# ad2addon.net
KiCad netlist of a schematic drawn in Altium Designer
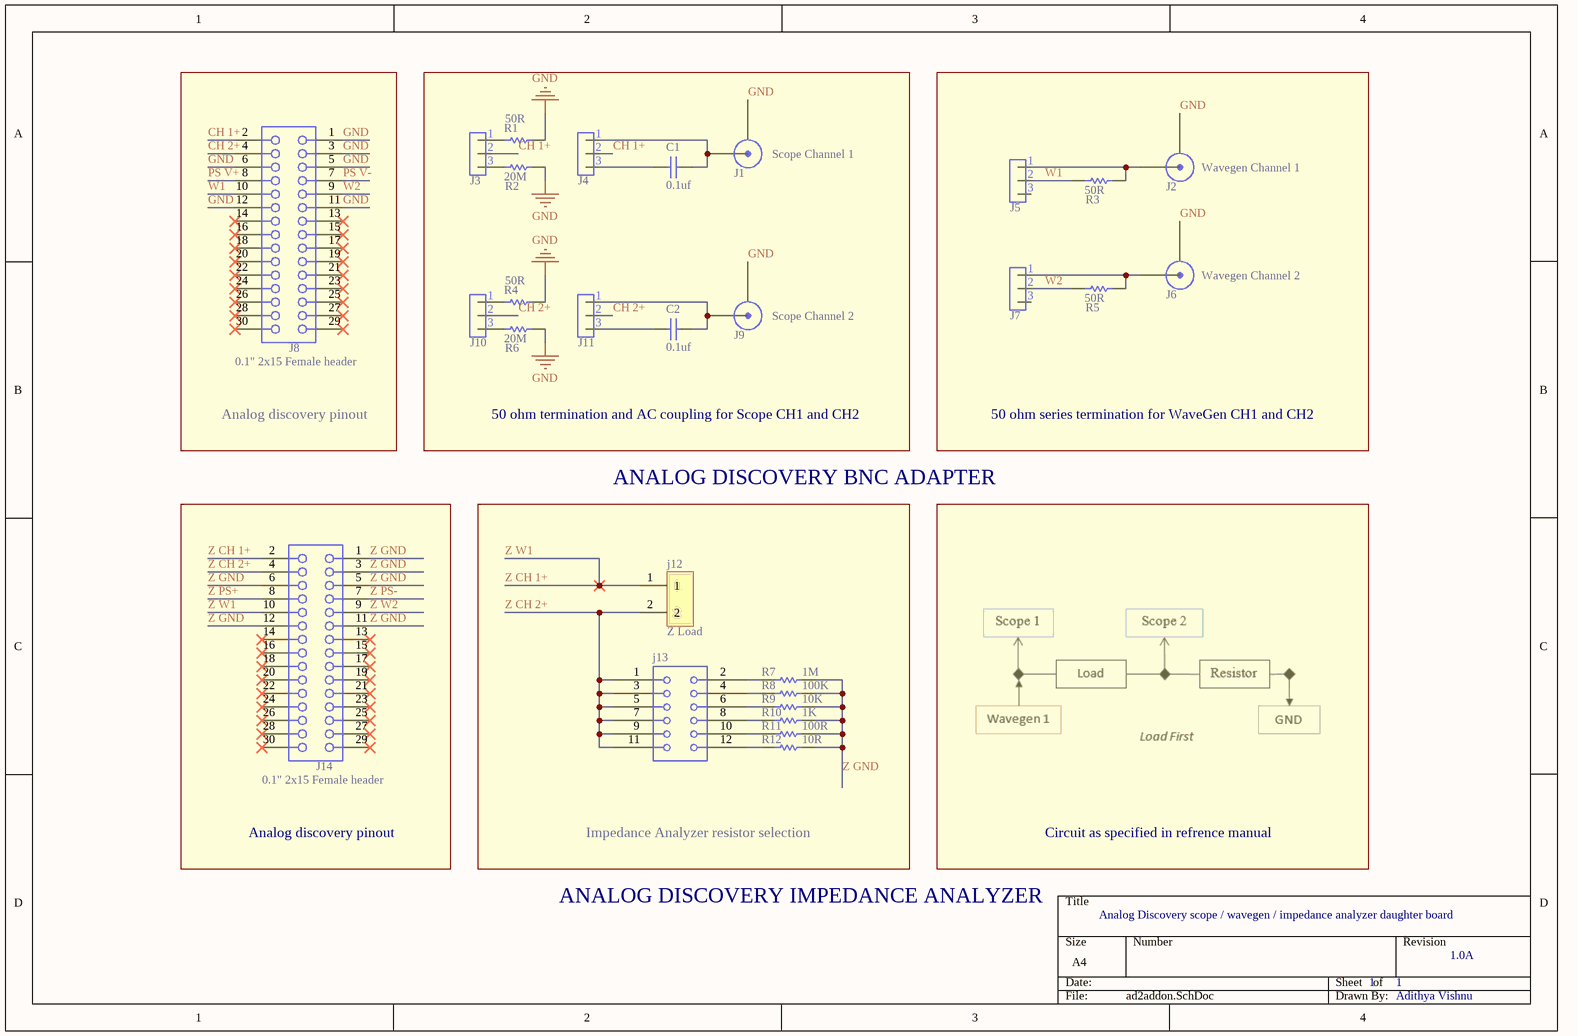
[diagram p0: ad2addon.SchDoc]

(export (version "E")
  (design (tool "Eeschema 10.0.6"))
  (components
    (comp (ref "C1")
      (value "0.1uf")
      (footprint "CAPC2013X94X50NL20T25")
      (description "CAP")
      (libsource (lib "CommunityVault") (part "CMP-126791-4"))
    )
    (comp (ref "C2")
      (value "0.1uf")
      (footprint "CAPC2013X94X50NL20T25")
      (description "CAP")
      (libsource (lib "CommunityVault") (part "CMP-126791-4"))
    )
    (comp (ref "J1")
      (value "Amphenol 031-5431-2010")
      (footprint "PCB-bp7jxlavj6ad2jzc7otg-1")
      (description "Right Angle 50Ohm Thru Hole Bulkhead Fitting BNC Conn, jack, Solder Term Nickel")
      (fields (field (name "PART PLACEMENT") "Scope Channel 1"))
      (libsource (lib "CommunityVault") (part "CMP-8fb544cbd9675072-1"))
    )
    (comp (ref "J2")
      (value "Amphenol 031-5431-2010")
      (footprint "PCB-bp7jxlavj6ad2jzc7otg-1")
      (description "Right Angle 50Ohm Thru Hole Bulkhead Fitting BNC Conn, jack, Solder Term Nickel")
      (fields (field (name "PART PLACEMENT") "Wavegen Channel 1"))
      (libsource (lib "CommunityVault") (part "CMP-8fb544cbd9675072-1"))
    )
    (comp (ref "J3")
      (value "SYM-52d299a8d8748d15-1")
      (footprint "PCB-vkgeqjtjqx6hhmcxuagx-1")
      (description "AMPMODU 3 Position 2.54 mm Single Row Through-Hole Straight Breakaway Header")
      (libsource (lib "CommunityVault") (part "SYM-52d299a8d8748d15-1"))
    )
    (comp (ref "J4")
      (value "SYM-52d299a8d8748d15-1")
      (footprint "PCB-vkgeqjtjqx6hhmcxuagx-1")
      (description "AMPMODU 3 Position 2.54 mm Single Row Through-Hole Straight Breakaway Header")
      (libsource (lib "CommunityVault") (part "SYM-52d299a8d8748d15-1"))
    )
    (comp (ref "J5")
      (value "SYM-52d299a8d8748d15-1")
      (footprint "PCB-vkgeqjtjqx6hhmcxuagx-1")
      (description "AMPMODU 3 Position 2.54 mm Single Row Through-Hole Straight Breakaway Header")
      (libsource (lib "CommunityVault") (part "SYM-52d299a8d8748d15-1"))
    )
    (comp (ref "J6")
      (value "Amphenol 031-5431-2010")
      (footprint "PCB-bp7jxlavj6ad2jzc7otg-1")
      (description "Right Angle 50Ohm Thru Hole Bulkhead Fitting BNC Conn, jack, Solder Term Nickel")
      (fields (field (name "PART PLACEMENT") "Wavegen Channel 2"))
      (libsource (lib "CommunityVault") (part "CMP-8fb544cbd9675072-1"))
    )
    (comp (ref "J7")
      (value "SYM-52d299a8d8748d15-1")
      (footprint "PCB-vkgeqjtjqx6hhmcxuagx-1")
      (description "AMPMODU 3 Position 2.54 mm Single Row Through-Hole Straight Breakaway Header")
      (libsource (lib "CommunityVault") (part "SYM-52d299a8d8748d15-1"))
    )
    (comp (ref "J8")
      (value "0.1\" 2x15 Female header")
      (footprint "SMTC-ESQ-115-13-X-D")
      (fields (field (name "MANUFACTURER PART NUMBER") "ESQ-115-13-G-D"))
      (libsource (lib "CommunityVault") (part "SMTC-ESQ-115-13-X-D"))
    )
    (comp (ref "J9")
      (value "Amphenol 031-5431-2010")
      (footprint "PCB-bp7jxlavj6ad2jzc7otg-1")
      (description "Right Angle 50Ohm Thru Hole Bulkhead Fitting BNC Conn, jack, Solder Term Nickel")
      (fields (field (name "PART PLACEMENT") "Scope Channel 2"))
      (libsource (lib "CommunityVault") (part "CMP-8fb544cbd9675072-1"))
    )
    (comp (ref "J10")
      (value "SYM-52d299a8d8748d15-1")
      (footprint "PCB-vkgeqjtjqx6hhmcxuagx-1")
      (description "AMPMODU 3 Position 2.54 mm Single Row Through-Hole Straight Breakaway Header")
      (libsource (lib "CommunityVault") (part "SYM-52d299a8d8748d15-1"))
    )
    (comp (ref "J11")
      (value "SYM-52d299a8d8748d15-1")
      (footprint "PCB-vkgeqjtjqx6hhmcxuagx-1")
      (description "AMPMODU 3 Position 2.54 mm Single Row Through-Hole Straight Breakaway Header")
      (libsource (lib "CommunityVault") (part "SYM-52d299a8d8748d15-1"))
    )
    (comp (ref "j12")
      (value "SYM-ced9058a17fd111e-1")
      (footprint "PCB-7j6xxwhkpc3kmbxd3myr-1")
      (description "Connector Terminal Blocks Receptacle 2 Position 5.08mm Solder Straight Thru-Hole 13.5A/Contact")
      (libsource (lib "CommunityVault") (part "CMP-50ff9bac89d88f38-17"))
    )
    (comp (ref "j13")
      (value "TE Connectivity / AMP 826656-6")
      (footprint "PCB-lq5xkcy8zqh038dq8ik0-1")
      (description "Conn Unshrouded Header HDR 12 POS 2.54mm Solder ST Thru-Hole Carton")
      (fields (field (name "MANUFACTURER PART NUMBER") "826656-6"))
      (libsource (lib "CommunityVault") (part "CMP-a42c6f58fc837beb-1"))
    )
    (comp (ref "J14")
      (value "0.1\" 2x15 Female header")
      (footprint "SMTC-ESQ-115-13-X-D")
      (fields (field (name "MANUFACTURER PART NUMBER") "ESQ-115-13-G-D"))
      (libsource (lib "CommunityVault") (part "CMP-4026240-2"))
    )
    (comp (ref "R1")
      (value "50R")
      (footprint "RESC2013X60X35LL10T20")
      (description "Res Thick Film 0805")
      (libsource (lib "CommunityVault") (part "CMP-4762415-2"))
    )
    (comp (ref "R2")
      (value "20M")
      (footprint "RESC2013X60X35LL10T20")
      (description "Res Thick Film 0805 20M Ohm 5% 1/8W 200ppm/C Molded SMD SMD Paper T/R")
      (fields (field (name "MANUFACTURER PART NUMBER") "RC0805JR-0720ML"))
      (libsource (lib "CommunityVault") (part "CMP-4762415-2"))
    )
    (comp (ref "R3")
      (value "50R")
      (footprint "RESC2013X60X35LL10T20")
      (description "Res Thick Film 0805")
      (libsource (lib "CommunityVault") (part "CMP-4762415-2"))
    )
    (comp (ref "R4")
      (value "50R")
      (footprint "RESC2013X60X35LL10T20")
      (description "Res Thick Film 0805")
      (libsource (lib "CommunityVault") (part "CMP-4762415-2"))
    )
    (comp (ref "R5")
      (value "50R")
      (footprint "RESC2013X60X35LL10T20")
      (description "Res Thick Film 0805")
      (libsource (lib "CommunityVault") (part "CMP-4762415-2"))
    )
    (comp (ref "R6")
      (value "20M")
      (footprint "RESC2013X60X35LL10T20")
      (description "Res Thick Film 0805 20M Ohm 5% 1/8W 200ppm/C Molded SMD SMD Paper T/R")
      (fields (field (name "MANUFACTURER PART NUMBER") "RC0805JR-0720ML"))
      (libsource (lib "CommunityVault") (part "CMP-4762415-2"))
    )
    (comp (ref "R7")
      (value "1M")
      (footprint "RESC2013X60X35LL10T20")
      (description "Res Thick Film 0805 20M Ohm 5% 1/8W 200ppm/C Molded SMD SMD Paper T/R")
      (fields (field (name "MANUFACTURER PART NUMBER") "RC0805JR-0720ML"))
      (libsource (lib "CommunityVault") (part "CMP-4762415-2"))
    )
    (comp (ref "R8")
      (value "100K")
      (footprint "RESC2013X60X35LL10T20")
      (description "Res Thick Film 0805 20M Ohm 5% 1/8W 200ppm/C Molded SMD SMD Paper T/R")
      (fields (field (name "MANUFACTURER PART NUMBER") "RC0805JR-0720ML"))
      (libsource (lib "CommunityVault") (part "CMP-4762415-2"))
    )
    (comp (ref "R9")
      (value "10K")
      (footprint "RESC2013X60X35LL10T20")
      (description "Res Thick Film 0805 20M Ohm 5% 1/8W 200ppm/C Molded SMD SMD Paper T/R")
      (fields (field (name "MANUFACTURER PART NUMBER") "RC0805JR-0720ML"))
      (libsource (lib "CommunityVault") (part "CMP-4762415-2"))
    )
    (comp (ref "R10")
      (value "1K")
      (footprint "RESC2013X60X35LL10T20")
      (description "Res Thick Film 0805 20M Ohm 5% 1/8W 200ppm/C Molded SMD SMD Paper T/R")
      (fields (field (name "MANUFACTURER PART NUMBER") "RC0805JR-0720ML"))
      (libsource (lib "CommunityVault") (part "CMP-4762415-2"))
    )
    (comp (ref "R11")
      (value "100R")
      (footprint "RESC2013X60X35LL10T20")
      (description "Res Thick Film 0805 20M Ohm 5% 1/8W 200ppm/C Molded SMD SMD Paper T/R")
      (fields (field (name "MANUFACTURER PART NUMBER") "RC0805JR-0720ML"))
      (libsource (lib "CommunityVault") (part "CMP-4762415-2"))
    )
    (comp (ref "R12")
      (value "10R")
      (footprint "RESC2013X60X35LL10T20")
      (description "Res Thick Film 0805 20M Ohm 5% 1/8W 200ppm/C Molded SMD SMD Paper T/R")
      (fields (field (name "MANUFACTURER PART NUMBER") "RC0805JR-0720ML"))
      (libsource (lib "CommunityVault") (part "CMP-4762415-2"))
    )
  )
  (nets
    (net (code "1") (name "/CH 1+") (class "Default")
      (node (ref "J3") (pin "2") (pinfunction "2_2") (pintype "passive"))
      (node (ref "J4") (pin "2") (pinfunction "2_2") (pintype "passive"))
      (node (ref "J8") (pin "2") (pinfunction "2_2") (pintype "passive"))
    )
    (net (code "2") (name "/CH 2+") (class "Default")
      (node (ref "J10") (pin "2") (pinfunction "2_2") (pintype "passive"))
      (node (ref "J11") (pin "2") (pinfunction "2_2") (pintype "passive"))
      (node (ref "J8") (pin "4") (pinfunction "4_4") (pintype "passive"))
    )
    (net (code "3") (name "/PS V+") (class "Default")
      (node (ref "J8") (pin "8") (pinfunction "8_8") (pintype "passive"))
    )
    (net (code "4") (name "/PS V-") (class "Default")
      (node (ref "J8") (pin "7") (pinfunction "7_7") (pintype "passive"))
    )
    (net (code "5") (name "/W1") (class "Default")
      (node (ref "J5") (pin "2") (pinfunction "2_2") (pintype "passive"))
      (node (ref "J8") (pin "10") (pinfunction "10_10") (pintype "passive"))
      (node (ref "R3") (pin "2") (pinfunction "2_2") (pintype "passive"))
    )
    (net (code "6") (name "/W2") (class "Default")
      (node (ref "J7") (pin "2") (pinfunction "2_2") (pintype "passive"))
      (node (ref "J8") (pin "9") (pinfunction "9_9") (pintype "passive"))
      (node (ref "R5") (pin "2") (pinfunction "2_2") (pintype "passive"))
    )
    (net (code "7") (name "/Z CH 1+") (class "Default")
      (node (ref "J14") (pin "10") (pinfunction "10_10") (pintype "passive"))
      (node (ref "J14") (pin "2") (pinfunction "2_2") (pintype "passive"))
      (node (ref "j12") (pin "1") (pinfunction "1_1") (pintype "passive"))
    )
    (net (code "8") (name "/Z CH 2+") (class "Default")
      (node (ref "J14") (pin "4") (pinfunction "4_4") (pintype "passive"))
      (node (ref "j12") (pin "2") (pinfunction "2_2") (pintype "passive"))
      (node (ref "j13") (pin "1") (pinfunction "1_1") (pintype "passive"))
      (node (ref "j13") (pin "11") (pinfunction "11_11") (pintype "passive"))
      (node (ref "j13") (pin "3") (pinfunction "3_3") (pintype "passive"))
      (node (ref "j13") (pin "5") (pinfunction "5_5") (pintype "passive"))
      (node (ref "j13") (pin "7") (pinfunction "7_7") (pintype "passive"))
      (node (ref "j13") (pin "9") (pinfunction "9_9") (pintype "passive"))
    )
    (net (code "9") (name "/Z GND") (class "Default")
      (node (ref "J14") (pin "1") (pinfunction "1_1") (pintype "passive"))
      (node (ref "J14") (pin "11") (pinfunction "11_11") (pintype "passive"))
      (node (ref "J14") (pin "12") (pinfunction "12_12") (pintype "passive"))
      (node (ref "J14") (pin "3") (pinfunction "3_3") (pintype "passive"))
      (node (ref "J14") (pin "5") (pinfunction "5_5") (pintype "passive"))
      (node (ref "J14") (pin "6") (pinfunction "6_6") (pintype "passive"))
      (node (ref "R10") (pin "1") (pinfunction "1_1") (pintype "passive"))
      (node (ref "R11") (pin "1") (pinfunction "1_1") (pintype "passive"))
      (node (ref "R12") (pin "1") (pinfunction "1_1") (pintype "passive"))
      (node (ref "R7") (pin "1") (pinfunction "1_1") (pintype "passive"))
      (node (ref "R8") (pin "1") (pinfunction "1_1") (pintype "passive"))
      (node (ref "R9") (pin "1") (pinfunction "1_1") (pintype "passive"))
    )
    (net (code "10") (name "/Z PS+") (class "Default")
      (node (ref "J14") (pin "8") (pinfunction "8_8") (pintype "passive"))
    )
    (net (code "11") (name "/Z PS-") (class "Default")
      (node (ref "J14") (pin "7") (pinfunction "7_7") (pintype "passive"))
    )
    (net (code "12") (name "/Z W2") (class "Default")
      (node (ref "J14") (pin "9") (pinfunction "9_9") (pintype "passive"))
    )
    (net (code "13") (name "GND") (class "Default")
      (node (ref "J1") (pin "2") (pinfunction "2_2") (pintype "passive"))
      (node (ref "J2") (pin "2") (pinfunction "2_2") (pintype "passive"))
      (node (ref "J6") (pin "2") (pinfunction "2_2") (pintype "passive"))
      (node (ref "J8") (pin "1") (pinfunction "1_1") (pintype "passive"))
      (node (ref "J8") (pin "11") (pinfunction "11_11") (pintype "passive"))
      (node (ref "J8") (pin "12") (pinfunction "12_12") (pintype "passive"))
      (node (ref "J8") (pin "3") (pinfunction "3_3") (pintype "passive"))
      (node (ref "J8") (pin "5") (pinfunction "5_5") (pintype "passive"))
      (node (ref "J8") (pin "6") (pinfunction "6_6") (pintype "passive"))
      (node (ref "J9") (pin "2") (pinfunction "2_2") (pintype "passive"))
      (node (ref "R1") (pin "1") (pinfunction "1_1") (pintype "passive"))
      (node (ref "R2") (pin "1") (pinfunction "1_1") (pintype "passive"))
      (node (ref "R4") (pin "1") (pinfunction "1_1") (pintype "passive"))
      (node (ref "R6") (pin "1") (pinfunction "1_1") (pintype "passive"))
    )
    (net (code "14") (name "Net-(C1-Pad1)") (class "Default")
      (node (ref "C1") (pin "1") (pinfunction "1_1") (pintype "passive"))
      (node (ref "J4") (pin "3") (pinfunction "3_3") (pintype "passive"))
    )
    (net (code "15") (name "Net-(C1-Pad2)") (class "Default")
      (node (ref "C1") (pin "2") (pinfunction "2_2") (pintype "passive"))
      (node (ref "J1") (pin "1") (pinfunction "1_1") (pintype "passive"))
      (node (ref "J4") (pin "1") (pinfunction "1_1") (pintype "passive"))
    )
    (net (code "16") (name "Net-(C2-Pad1)") (class "Default")
      (node (ref "C2") (pin "1") (pinfunction "1_1") (pintype "passive"))
      (node (ref "J11") (pin "3") (pinfunction "3_3") (pintype "passive"))
    )
    (net (code "17") (name "Net-(C2-Pad2)") (class "Default")
      (node (ref "C2") (pin "2") (pinfunction "2_2") (pintype "passive"))
      (node (ref "J11") (pin "1") (pinfunction "1_1") (pintype "passive"))
      (node (ref "J9") (pin "1") (pinfunction "1_1") (pintype "passive"))
    )
    (net (code "18") (name "Net-(J2-Pad1)") (class "Default")
      (node (ref "J2") (pin "1") (pinfunction "1_1") (pintype "passive"))
      (node (ref "J5") (pin "1") (pinfunction "1_1") (pintype "passive"))
      (node (ref "R3") (pin "1") (pinfunction "1_1") (pintype "passive"))
    )
    (net (code "19") (name "Net-(J3-Pad1)") (class "Default")
      (node (ref "J3") (pin "1") (pinfunction "1_1") (pintype "passive"))
      (node (ref "R1") (pin "2") (pinfunction "2_2") (pintype "passive"))
    )
    (net (code "20") (name "Net-(J3-Pad3)") (class "Default")
      (node (ref "J3") (pin "3") (pinfunction "3_3") (pintype "passive"))
      (node (ref "R2") (pin "2") (pinfunction "2_2") (pintype "passive"))
    )
    (net (code "21") (name "Net-(J6-Pad1)") (class "Default")
      (node (ref "J6") (pin "1") (pinfunction "1_1") (pintype "passive"))
      (node (ref "J7") (pin "1") (pinfunction "1_1") (pintype "passive"))
      (node (ref "R5") (pin "1") (pinfunction "1_1") (pintype "passive"))
    )
    (net (code "22") (name "Net-(J10-Pad1)") (class "Default")
      (node (ref "J10") (pin "1") (pinfunction "1_1") (pintype "passive"))
      (node (ref "R4") (pin "2") (pinfunction "2_2") (pintype "passive"))
    )
    (net (code "23") (name "Net-(J10-Pad3)") (class "Default")
      (node (ref "J10") (pin "3") (pinfunction "3_3") (pintype "passive"))
      (node (ref "R6") (pin "2") (pinfunction "2_2") (pintype "passive"))
    )
    (net (code "24") (name "Net-(R7-Pad2)") (class "Default")
      (node (ref "R7") (pin "2") (pinfunction "2_2") (pintype "passive"))
      (node (ref "j13") (pin "2") (pinfunction "2_2") (pintype "passive"))
    )
    (net (code "25") (name "Net-(R8-Pad2)") (class "Default")
      (node (ref "R8") (pin "2") (pinfunction "2_2") (pintype "passive"))
      (node (ref "j13") (pin "4") (pinfunction "4_4") (pintype "passive"))
    )
    (net (code "26") (name "Net-(R9-Pad2)") (class "Default")
      (node (ref "R9") (pin "2") (pinfunction "2_2") (pintype "passive"))
      (node (ref "j13") (pin "6") (pinfunction "6_6") (pintype "passive"))
    )
    (net (code "27") (name "Net-(R10-Pad2)") (class "Default")
      (node (ref "R10") (pin "2") (pinfunction "2_2") (pintype "passive"))
      (node (ref "j13") (pin "8") (pinfunction "8_8") (pintype "passive"))
    )
    (net (code "28") (name "Net-(R11-Pad2)") (class "Default")
      (node (ref "R11") (pin "2") (pinfunction "2_2") (pintype "passive"))
      (node (ref "j13") (pin "10") (pinfunction "10_10") (pintype "passive"))
    )
    (net (code "29") (name "Net-(R12-Pad2)") (class "Default")
      (node (ref "R12") (pin "2") (pinfunction "2_2") (pintype "passive"))
      (node (ref "j13") (pin "12") (pinfunction "12_12") (pintype "passive"))
    )
    (net (code "30") (name "unconnected-(J5-Pad3)") (class "Default")
      (node (ref "J5") (pin "3") (pinfunction "3_3") (pintype "passive"))
    )
    (net (code "31") (name "unconnected-(J7-Pad3)") (class "Default")
      (node (ref "J7") (pin "3") (pinfunction "3_3") (pintype "passive"))
    )
    (net (code "32") (name "unconnected-(J8-Pad13)") (class "Default")
      (node (ref "J8") (pin "13") (pinfunction "13_13") (pintype "passive+no_connect"))
    )
    (net (code "33") (name "unconnected-(J8-Pad14)") (class "Default")
      (node (ref "J8") (pin "14") (pinfunction "14_14") (pintype "passive+no_connect"))
    )
    (net (code "34") (name "unconnected-(J8-Pad15)") (class "Default")
      (node (ref "J8") (pin "15") (pinfunction "15_15") (pintype "passive+no_connect"))
    )
    (net (code "35") (name "unconnected-(J8-Pad16)") (class "Default")
      (node (ref "J8") (pin "16") (pinfunction "16_16") (pintype "passive+no_connect"))
    )
    (net (code "36") (name "unconnected-(J8-Pad17)") (class "Default")
      (node (ref "J8") (pin "17") (pinfunction "17_17") (pintype "passive+no_connect"))
    )
    (net (code "37") (name "unconnected-(J8-Pad18)") (class "Default")
      (node (ref "J8") (pin "18") (pinfunction "18_18") (pintype "passive+no_connect"))
    )
    (net (code "38") (name "unconnected-(J8-Pad19)") (class "Default")
      (node (ref "J8") (pin "19") (pinfunction "19_19") (pintype "passive+no_connect"))
    )
    (net (code "39") (name "unconnected-(J8-Pad20)") (class "Default")
      (node (ref "J8") (pin "20") (pinfunction "20_20") (pintype "passive+no_connect"))
    )
    (net (code "40") (name "unconnected-(J8-Pad21)") (class "Default")
      (node (ref "J8") (pin "21") (pinfunction "21_21") (pintype "passive+no_connect"))
    )
    (net (code "41") (name "unconnected-(J8-Pad22)") (class "Default")
      (node (ref "J8") (pin "22") (pinfunction "22_22") (pintype "passive+no_connect"))
    )
    (net (code "42") (name "unconnected-(J8-Pad23)") (class "Default")
      (node (ref "J8") (pin "23") (pinfunction "23_23") (pintype "passive+no_connect"))
    )
    (net (code "43") (name "unconnected-(J8-Pad24)") (class "Default")
      (node (ref "J8") (pin "24") (pinfunction "24_24") (pintype "passive+no_connect"))
    )
    (net (code "44") (name "unconnected-(J8-Pad25)") (class "Default")
      (node (ref "J8") (pin "25") (pinfunction "25_25") (pintype "passive+no_connect"))
    )
    (net (code "45") (name "unconnected-(J8-Pad26)") (class "Default")
      (node (ref "J8") (pin "26") (pinfunction "26_26") (pintype "passive+no_connect"))
    )
    (net (code "46") (name "unconnected-(J8-Pad27)") (class "Default")
      (node (ref "J8") (pin "27") (pinfunction "27_27") (pintype "passive+no_connect"))
    )
    (net (code "47") (name "unconnected-(J8-Pad28)") (class "Default")
      (node (ref "J8") (pin "28") (pinfunction "28_28") (pintype "passive+no_connect"))
    )
    (net (code "48") (name "unconnected-(J8-Pad29)") (class "Default")
      (node (ref "J8") (pin "29") (pinfunction "29_29") (pintype "passive+no_connect"))
    )
    (net (code "49") (name "unconnected-(J8-Pad30)") (class "Default")
      (node (ref "J8") (pin "30") (pinfunction "30_30") (pintype "passive+no_connect"))
    )
    (net (code "50") (name "unconnected-(J14-Pad13)") (class "Default")
      (node (ref "J14") (pin "13") (pinfunction "13_13") (pintype "passive+no_connect"))
    )
    (net (code "51") (name "unconnected-(J14-Pad14)") (class "Default")
      (node (ref "J14") (pin "14") (pinfunction "14_14") (pintype "passive+no_connect"))
    )
    (net (code "52") (name "unconnected-(J14-Pad15)") (class "Default")
      (node (ref "J14") (pin "15") (pinfunction "15_15") (pintype "passive+no_connect"))
    )
    (net (code "53") (name "unconnected-(J14-Pad16)") (class "Default")
      (node (ref "J14") (pin "16") (pinfunction "16_16") (pintype "passive+no_connect"))
    )
    (net (code "54") (name "unconnected-(J14-Pad17)") (class "Default")
      (node (ref "J14") (pin "17") (pinfunction "17_17") (pintype "passive+no_connect"))
    )
    (net (code "55") (name "unconnected-(J14-Pad18)") (class "Default")
      (node (ref "J14") (pin "18") (pinfunction "18_18") (pintype "passive+no_connect"))
    )
    (net (code "56") (name "unconnected-(J14-Pad19)") (class "Default")
      (node (ref "J14") (pin "19") (pinfunction "19_19") (pintype "passive+no_connect"))
    )
    (net (code "57") (name "unconnected-(J14-Pad20)") (class "Default")
      (node (ref "J14") (pin "20") (pinfunction "20_20") (pintype "passive+no_connect"))
    )
    (net (code "58") (name "unconnected-(J14-Pad21)") (class "Default")
      (node (ref "J14") (pin "21") (pinfunction "21_21") (pintype "passive+no_connect"))
    )
    (net (code "59") (name "unconnected-(J14-Pad22)") (class "Default")
      (node (ref "J14") (pin "22") (pinfunction "22_22") (pintype "passive+no_connect"))
    )
    (net (code "60") (name "unconnected-(J14-Pad23)") (class "Default")
      (node (ref "J14") (pin "23") (pinfunction "23_23") (pintype "passive+no_connect"))
    )
    (net (code "61") (name "unconnected-(J14-Pad24)") (class "Default")
      (node (ref "J14") (pin "24") (pinfunction "24_24") (pintype "passive+no_connect"))
    )
    (net (code "62") (name "unconnected-(J14-Pad25)") (class "Default")
      (node (ref "J14") (pin "25") (pinfunction "25_25") (pintype "passive+no_connect"))
    )
    (net (code "63") (name "unconnected-(J14-Pad26)") (class "Default")
      (node (ref "J14") (pin "26") (pinfunction "26_26") (pintype "passive+no_connect"))
    )
    (net (code "64") (name "unconnected-(J14-Pad27)") (class "Default")
      (node (ref "J14") (pin "27") (pinfunction "27_27") (pintype "passive+no_connect"))
    )
    (net (code "65") (name "unconnected-(J14-Pad28)") (class "Default")
      (node (ref "J14") (pin "28") (pinfunction "28_28") (pintype "passive+no_connect"))
    )
    (net (code "66") (name "unconnected-(J14-Pad29)") (class "Default")
      (node (ref "J14") (pin "29") (pinfunction "29_29") (pintype "passive+no_connect"))
    )
    (net (code "67") (name "unconnected-(J14-Pad30)") (class "Default")
      (node (ref "J14") (pin "30") (pinfunction "30_30") (pintype "passive+no_connect"))
    )
  )
)
